# PWM_Input.net
KiCad netlist of a schematic drawn in Altium Designer
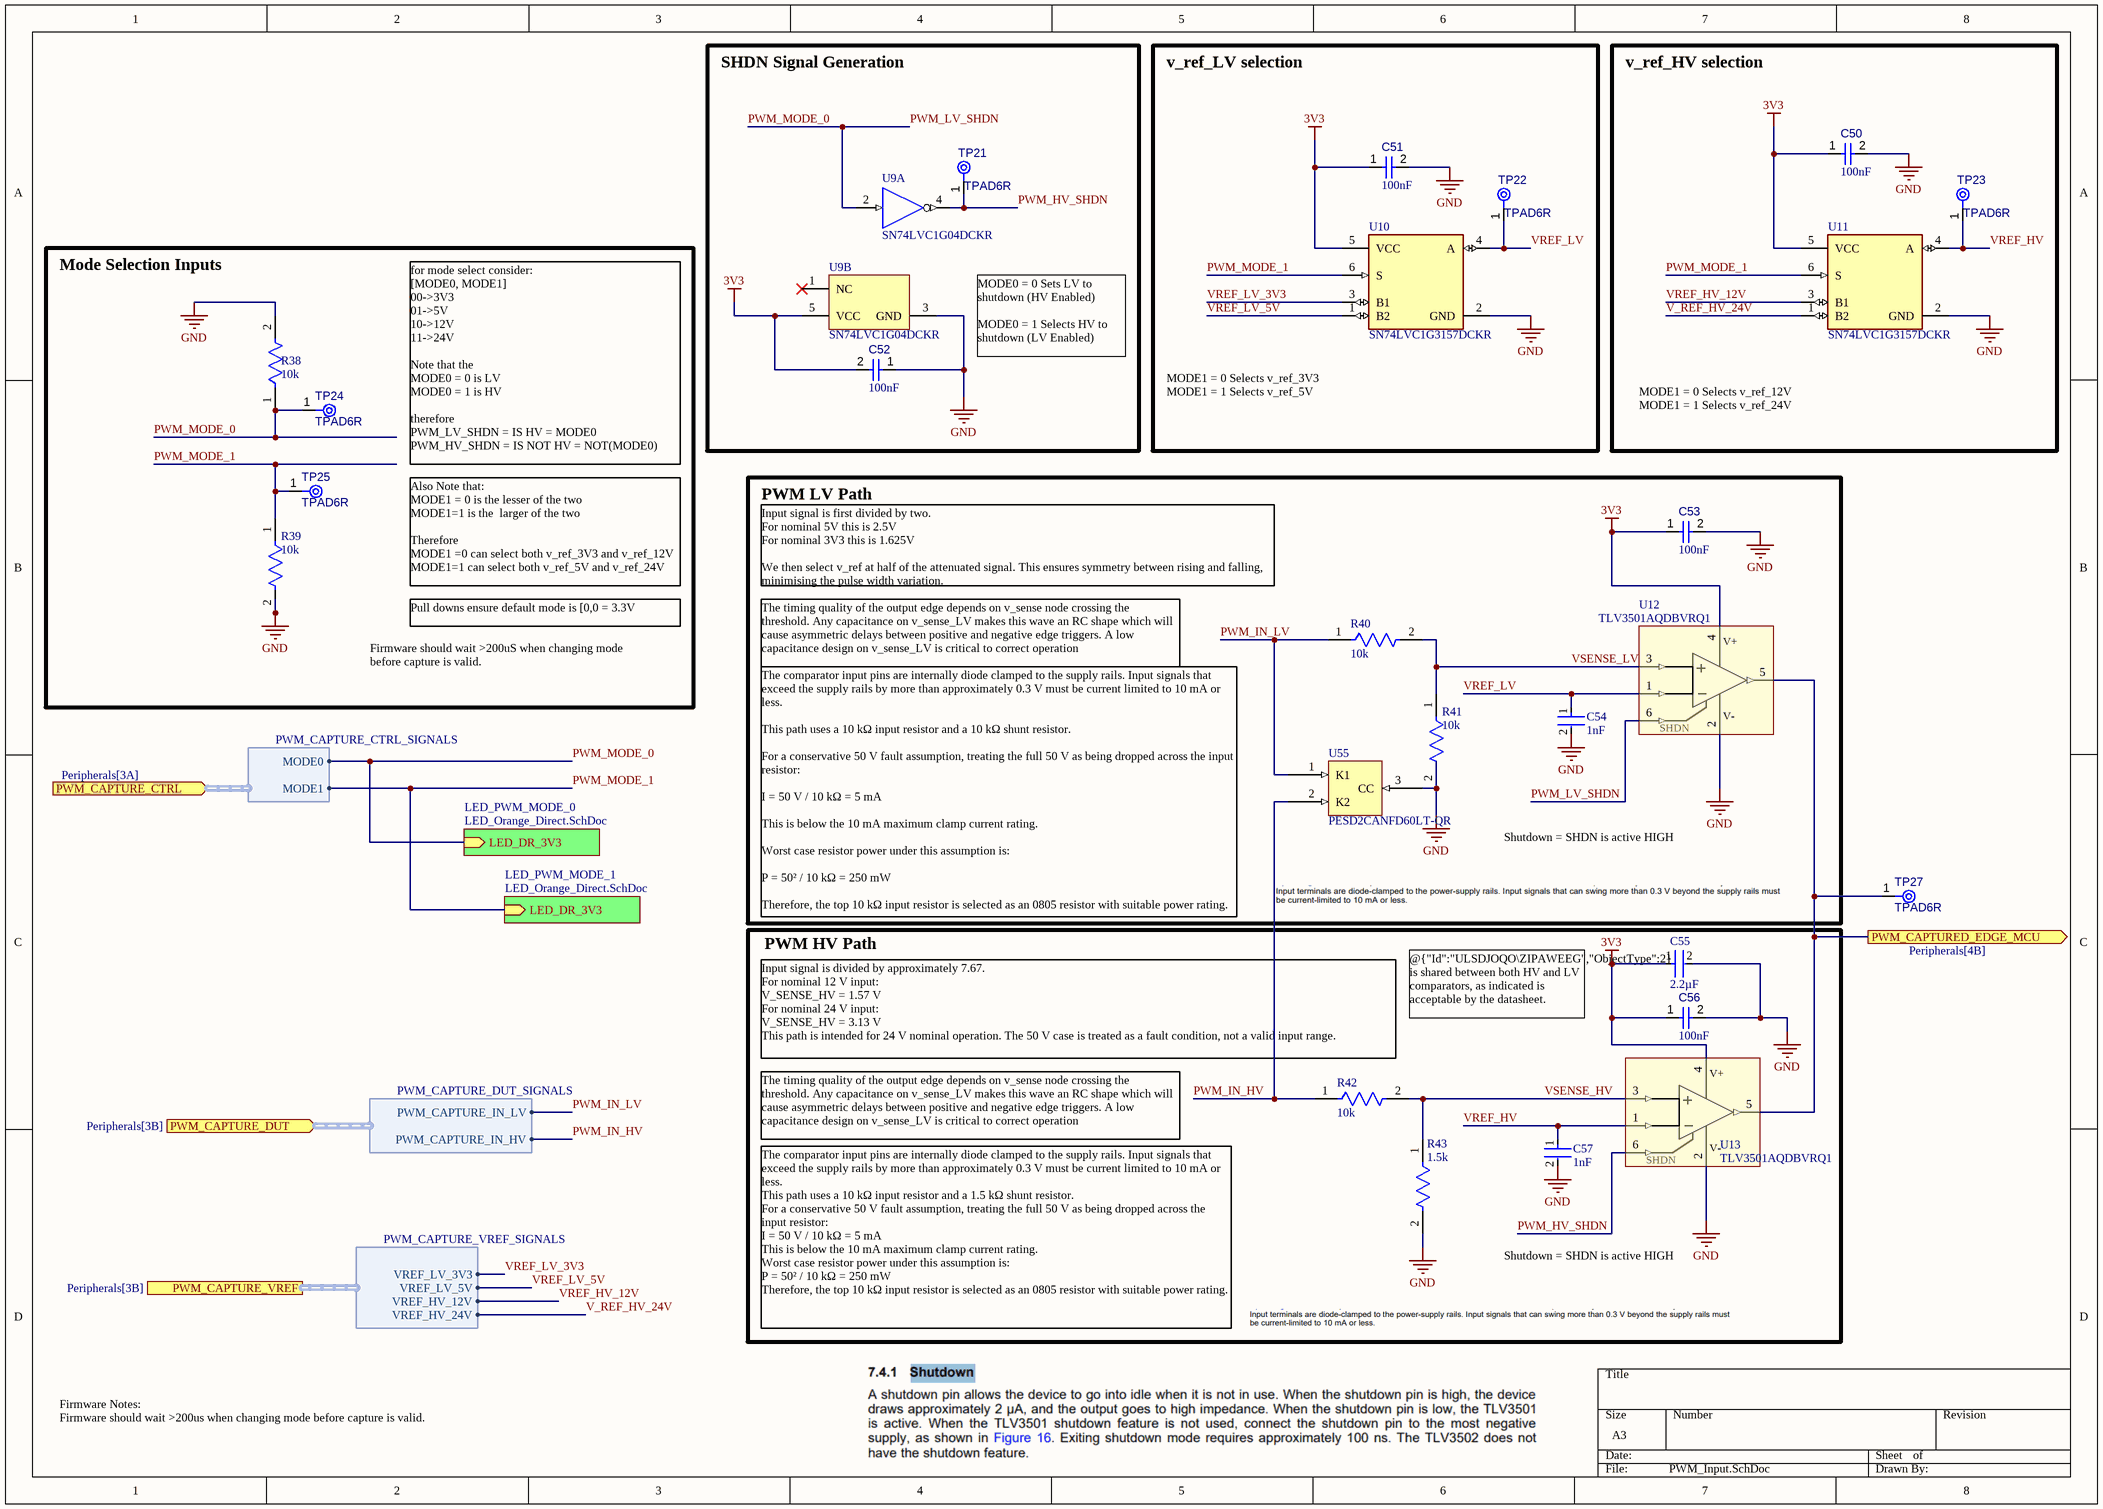
[diagram p0:  PWM_Input.SchDoc]

(export (version "E")
  (design (tool "Eeschema 10.0.6"))
  (components
    (comp (ref "C50")
      (value "100nF")
      (footprint "CAPC1608X90X40ML10T20")
      (description "Chip Capacitor, 100 nF, +/- 10%, 50 V, 0603 (1608 Metric)")
      (fields (field (name "TOLERANCE") "10%") (field (name "Comment") "Capacitor 100 nF +/-10% 50 V 0603"))
      (libsource (lib "HIL RIG FYP") (part "CAP-NP-2"))
    )
    (comp (ref "C51")
      (value "100nF")
      (footprint "CAPC1608X90X40NL10T20")
      (description "Chip Capacitor, 100 nF, +/- 10%, 50 V, 0603 (1608 Metric)")
      (fields (field (name "TOLERANCE") "10%") (field (name "Comment") "Capacitor 100 nF +/-10% 50 V 0603"))
      (libsource (lib "HIL RIG FYP") (part "CAP-NP-2"))
    )
    (comp (ref "C52")
      (value "100nF")
      (footprint "CAPC1608X90X40ML10T20")
      (description "Chip Capacitor, 100 nF, +/- 10%, 50 V, 0603 (1608 Metric)")
      (fields (field (name "TOLERANCE") "10%") (field (name "Comment") "Capacitor 100 nF +/-10% 50 V 0603"))
      (libsource (lib "HIL RIG FYP") (part "CAP-NP-2"))
    )
    (comp (ref "C53")
      (value "100nF")
      (footprint "CAPC1608X90X40ML10T20")
      (description "Chip Capacitor, 100 nF, +/- 10%, 50 V, 0603 (1608 Metric)")
      (fields (field (name "TOLERANCE") "10%") (field (name "Comment") "Capacitor 100 nF +/-10% 50 V 0603"))
      (libsource (lib "HIL RIG FYP") (part "CAP-NP-2"))
    )
    (comp (ref "C54")
      (value "1nF")
      (footprint "FP-CC0603-DA-IPC_B")
      (description "16V 1nF X7R ±10% 0603 Multilayer Ceramic Capacitors MLCC - SMD/SMT ROHS")
      (fields (field (name "TOLERANCE") "10%") (field (name "Comment") "CC0603KRX7R7BB102"))
      (libsource (lib "HIL RIG FYP") (part "11868f565c42a9108669ba33697ecf6"))
    )
    (comp (ref "C55")
      (value "2.2µF")
      (footprint "FP-GRM188-0_1-e0_2_0_5-IPC_B")
      (description "10V 2.2uF X7R ±10% 0603 Multilayer Ceramic Capacitors MLCC - SMD/SMT ROHS")
      (fields (field (name "VOLTAGE") "10V") (field (name "TOLERANCE") "10%"))
      (libsource (lib "HIL RIG FYP") (part "11868f565c42a9108669ba33697ecf6"))
    )
    (comp (ref "C56")
      (value "100nF")
      (footprint "CAPC1608X90X40ML10T20")
      (description "Chip Capacitor, 100 nF, +/- 10%, 50 V, 0603 (1608 Metric)")
      (fields (field (name "TOLERANCE") "10%") (field (name "Comment") "Capacitor 100 nF +/-10% 50 V 0603"))
      (libsource (lib "HIL RIG FYP") (part "CAP-NP-2"))
    )
    (comp (ref "C57")
      (value "1nF")
      (footprint "FP-CC0603-DA-IPC_B")
      (description "16V 1nF X7R ±10% 0603 Multilayer Ceramic Capacitors MLCC - SMD/SMT ROHS")
      (fields (field (name "TOLERANCE") "10%") (field (name "Comment") "CC0603KRX7R7BB102"))
      (libsource (lib "HIL RIG FYP") (part "11868f565c42a9108669ba33697ecf6"))
    )
    (comp (ref "R38")
      (value "10k")
      (footprint "FP-RT0603-IPC_C")
      (description "Res Thin Film 0603 10K Ohm 0.1% 1/10W ¦25ppm/¦C SMD Paper T/R")
      (fields (field (name "TOLERANCE") "0.1%") (field (name "Comment") "RT0603BRD0710KL"))
      (libsource (lib "HIL RIG FYP") (part "1029c3af85768c4190bb7ad29bc67b5"))
    )
    (comp (ref "R39")
      (value "10k")
      (footprint "FP-RT0603-IPC_A")
      (description "Res Thin Film 0603 10K Ohm 0.1% 1/10W ¦25ppm/¦C SMD Paper T/R")
      (fields (field (name "TOLERANCE") "0.1%") (field (name "Comment") "RT0603BRD0710KL"))
      (libsource (lib "HIL RIG FYP") (part "1029c3af85768c4190bb7ad29bc67b5"))
    )
    (comp (ref "R40")
      (value "10k")
      (footprint "FP-ESR18-IPC_A")
      (description "Res Thick Film 1206 10K Ohm 1% 0.5W(1/2W) ±100ppm/C Pad SMD T/R Automotive AEC-Q200")
      (fields (field (name "TOLERANCE") "1%") (field (name "Comment") "ESR18EZPF1002"))
      (libsource (lib "HIL RIG FYP") (part "1029c3af85768c4190bb7ad29bc67b5"))
    )
    (comp (ref "R41")
      (value "10k")
      (footprint "FP-RT0603-IPC_A")
      (description "Res Thin Film 0603 10K Ohm 0.1% 1/10W ¦25ppm/¦C SMD Paper T/R")
      (fields (field (name "TOLERANCE") "0.1%") (field (name "Comment") "RT0603BRD0710KL"))
      (libsource (lib "HIL RIG FYP") (part "1029c3af85768c4190bb7ad29bc67b5"))
    )
    (comp (ref "R42")
      (value "10k")
      (footprint "FP-ESR18-IPC_A")
      (description "Res Thick Film 1206 10K Ohm 1% 0.5W(1/2W) ±100ppm/C Pad SMD T/R Automotive AEC-Q200")
      (fields (field (name "TOLERANCE") "1%") (field (name "Comment") "ESR18EZPF1002"))
      (libsource (lib "HIL RIG FYP") (part "1029c3af85768c4190bb7ad29bc67b5"))
    )
    (comp (ref "R43")
      (value "1.5k")
      (footprint "FP-RT0603-IPC_C")
      (description "Res Thin Film 0603 1.5K Ohm 0.1% 1/10W ±25ppm/°C Molded SMD SMD Paper T/R")
      (fields (field (name "TOLERANCE") "0.1%") (field (name "Comment") "RT0603BRD071K5L"))
      (libsource (lib "HIL RIG FYP") (part "1029c3af85768c4190bb7ad29bc67b5"))
    )
    (comp (ref "TP21")
      (value "TPAD6R")
      (footprint "TP06R")
      (description "0.6mm round")
      (libsource (lib "HIL RIG FYP") (part "CMP-001-0001-4"))
    )
    (comp (ref "TP22")
      (value "TPAD6R")
      (footprint "TP06R")
      (description "0.6mm round")
      (libsource (lib "HIL RIG FYP") (part "CMP-001-0001-4"))
    )
    (comp (ref "TP23")
      (value "TPAD6R")
      (footprint "TP06R")
      (description "0.6mm round")
      (libsource (lib "HIL RIG FYP") (part "CMP-001-0001-4"))
    )
    (comp (ref "TP24")
      (value "TPAD6R")
      (footprint "TP06R")
      (description "0.6mm round")
      (libsource (lib "HIL RIG FYP") (part "CMP-001-0001-4"))
    )
    (comp (ref "TP25")
      (value "TPAD6R")
      (footprint "TP06R")
      (description "0.6mm round")
      (libsource (lib "HIL RIG FYP") (part "CMP-001-0001-4"))
    )
    (comp (ref "TP27")
      (value "TPAD6R")
      (footprint "TP06R")
      (description "0.6mm round")
      (libsource (lib "HIL RIG FYP") (part "CMP-001-0001-4"))
    )
    (comp (ref "U9")
      (value "SN74LVC1G04DCKR")
      (footprint "DCK0005A_N")
      (description "IC SINGLE INVERTER GATE SC70-5 / Inverter 1-Element CMOS 5-Pin SC-70 T/R")
      (libsource (lib "HIL RIG FYP") (part "TI-SN74XXX1XX4-XX-5"))
    )
    (comp (ref "U10")
      (value "SN74LVC1G3157DCKR")
      (footprint "FP-DCK0006A-MFG")
      (description "Single-pole Double-throw Analog Switch SPDT, 1 Func, 1 Channel, Cmos, PDSO6")
      (libsource (lib "HIL RIG FYP") (part "0261a57985ab8eeec66806cf7caee19"))
    )
    (comp (ref "U11")
      (value "SN74LVC1G3157DCKR")
      (footprint "FP-DCK0006A-MFG")
      (description "Single-pole Double-throw Analog Switch SPDT, 1 Func, 1 Channel, Cmos, PDSO6")
      (libsource (lib "HIL RIG FYP") (part "0261a57985ab8eeec66806cf7caee19"))
    )
    (comp (ref "U12")
      (value "TLV3501AQDBVRQ1")
      (footprint "SOT95P280X145-6M")
      (fields (field (name "COPYRIGHT") "Copyright (C) 2025 Ultra Librarian. All rights reserved."))
      (libsource (lib "HIL RIG FYP") (part "TLV3501AQDBVRQ1"))
    )
    (comp (ref "U13")
      (value "TLV3501AQDBVRQ1")
      (footprint "SOT95P280X145-6M")
      (fields (field (name "COPYRIGHT") "Copyright (C) 2025 Ultra Librarian. All rights reserved."))
      (libsource (lib "HIL RIG FYP") (part "TLV3501AQDBVRQ1"))
    )
    (comp (ref "U55")
      (value "PESD2CANFD60LT-QR")
      (footprint "SOT95P230X110-3M")
      (description "Esd Protection Device, 79V, SOT-23-3 Rohs Compliant: Yes")
      (libsource (lib "HIL RIG FYP") (part "PESD2CANFD60LT-QR-Symbol-1"))
    )
  )
  (nets
    (net (code "4") (name "/PWM_CAPTURED_EDGE_MCU") (class "Default")
      (node (ref "TP27") (pin "1") (pinfunction "TP_1") (pintype "passive"))
      (node (ref "U12") (pin "5") (pinfunction "OUT_5") (pintype "output"))
      (node (ref "U13") (pin "5") (pinfunction "OUT_5") (pintype "output"))
    )
    (net (code "5") (name "/PWM_HV_SHDN") (class "Default")
      (node (ref "TP21") (pin "1") (pinfunction "TP_1") (pintype "passive"))
      (node (ref "U13") (pin "6") (pinfunction "SD_6") (pintype "input"))
      (node (ref "U9") (pin "4") (pinfunction "Y_4") (pintype "output"))
    )
    (net (code "6") (name "/PWM_IN_HV") (class "Default")
      (node (ref "R42") (pin "1") (pinfunction "1_1") (pintype "passive"))
      (node (ref "U55") (pin "2") (pinfunction "K2_2") (pintype "input"))
    )
    (net (code "7") (name "/PWM_IN_LV") (class "Default")
      (node (ref "R40") (pin "1") (pinfunction "1_1") (pintype "passive"))
      (node (ref "U55") (pin "1") (pinfunction "K1_1") (pintype "input"))
    )
    (net (code "8") (name "/PWM_LV_SHDN") (class "Default")
      (node (ref "R38") (pin "1") (pinfunction "1_1") (pintype "passive"))
      (node (ref "TP24") (pin "1") (pinfunction "TP_1") (pintype "passive"))
      (node (ref "U12") (pin "6") (pinfunction "SD_6") (pintype "input"))
      (node (ref "U9") (pin "2") (pinfunction "A_2") (pintype "input"))
    )
    (net (code "9") (name "/PWM_MODE_1") (class "Default")
      (node (ref "R39") (pin "1") (pinfunction "1_1") (pintype "passive"))
      (node (ref "TP25") (pin "1") (pinfunction "TP_1") (pintype "passive"))
      (node (ref "U10") (pin "6") (pinfunction "S_6") (pintype "input"))
      (node (ref "U11") (pin "6") (pinfunction "S_6") (pintype "input"))
    )
    (net (code "10") (name "/VREF_HV") (class "Default")
      (node (ref "C57") (pin "1") (pinfunction "1_1") (pintype "passive"))
      (node (ref "TP23") (pin "1") (pinfunction "TP_1") (pintype "passive"))
      (node (ref "U11") (pin "4") (pinfunction "A_4") (pintype "bidirectional"))
      (node (ref "U13") (pin "1") (pinfunction "IN-_1") (pintype "input"))
    )
    (net (code "11") (name "/VREF_HV_12V") (class "Default")
      (node (ref "U11") (pin "3") (pinfunction "B1_3") (pintype "bidirectional"))
    )
    (net (code "12") (name "/VREF_LV") (class "Default")
      (node (ref "C54") (pin "1") (pinfunction "1_1") (pintype "passive"))
      (node (ref "TP22") (pin "1") (pinfunction "TP_1") (pintype "passive"))
      (node (ref "U10") (pin "4") (pinfunction "A_4") (pintype "bidirectional"))
      (node (ref "U12") (pin "1") (pinfunction "IN-_1") (pintype "input"))
    )
    (net (code "13") (name "/VREF_LV_3V3") (class "Default")
      (node (ref "U10") (pin "3") (pinfunction "B1_3") (pintype "bidirectional"))
    )
    (net (code "14") (name "/VREF_LV_5V") (class "Default")
      (node (ref "U10") (pin "1") (pinfunction "B2_1") (pintype "bidirectional"))
    )
    (net (code "15") (name "/VSENSE_HV") (class "Default")
      (node (ref "R42") (pin "2") (pinfunction "2_2") (pintype "passive"))
      (node (ref "R43") (pin "1") (pinfunction "1_1") (pintype "passive"))
      (node (ref "U13") (pin "3") (pinfunction "IN+_3") (pintype "input"))
    )
    (net (code "16") (name "/VSENSE_LV") (class "Default")
      (node (ref "R40") (pin "2") (pinfunction "2_2") (pintype "passive"))
      (node (ref "R41") (pin "1") (pinfunction "1_1") (pintype "passive"))
      (node (ref "U12") (pin "3") (pinfunction "IN+_3") (pintype "input"))
    )
    (net (code "17") (name "/V_REF_HV_24V") (class "Default")
      (node (ref "U11") (pin "1") (pinfunction "B2_1") (pintype "bidirectional"))
    )
    (net (code "21") (name "3V3") (class "Default")
      (node (ref "C50") (pin "1") (pinfunction "1_1") (pintype "passive"))
      (node (ref "C51") (pin "1") (pinfunction "1_1") (pintype "passive"))
      (node (ref "C52") (pin "2") (pinfunction "2_2") (pintype "passive"))
      (node (ref "C53") (pin "1") (pinfunction "1_1") (pintype "passive"))
      (node (ref "C55") (pin "1") (pinfunction "1_1") (pintype "passive"))
      (node (ref "C56") (pin "1") (pinfunction "1_1") (pintype "passive"))
      (node (ref "U10") (pin "5") (pinfunction "VCC_5") (pintype "power_in"))
      (node (ref "U11") (pin "5") (pinfunction "VCC_5") (pintype "power_in"))
      (node (ref "U12") (pin "4") (pinfunction "V+_4") (pintype "power_in"))
      (node (ref "U13") (pin "4") (pinfunction "V+_4") (pintype "power_in"))
      (node (ref "U9") (pin "5") (pinfunction "VCC_5") (pintype "power_in"))
    )
    (net (code "22") (name "GND") (class "Default")
      (node (ref "C50") (pin "2") (pinfunction "2_2") (pintype "passive"))
      (node (ref "C51") (pin "2") (pinfunction "2_2") (pintype "passive"))
      (node (ref "C52") (pin "1") (pinfunction "1_1") (pintype "passive"))
      (node (ref "C53") (pin "2") (pinfunction "2_2") (pintype "passive"))
      (node (ref "C54") (pin "2") (pinfunction "2_2") (pintype "passive"))
      (node (ref "C55") (pin "2") (pinfunction "2_2") (pintype "passive"))
      (node (ref "C56") (pin "2") (pinfunction "2_2") (pintype "passive"))
      (node (ref "C57") (pin "2") (pinfunction "2_2") (pintype "passive"))
      (node (ref "R38") (pin "2") (pinfunction "2_2") (pintype "passive"))
      (node (ref "R39") (pin "2") (pinfunction "2_2") (pintype "passive"))
      (node (ref "R41") (pin "2") (pinfunction "2_2") (pintype "passive"))
      (node (ref "R43") (pin "2") (pinfunction "2_2") (pintype "passive"))
      (node (ref "U10") (pin "2") (pinfunction "GND_2") (pintype "power_in"))
      (node (ref "U11") (pin "2") (pinfunction "GND_2") (pintype "power_in"))
      (node (ref "U12") (pin "2") (pinfunction "V-_2") (pintype "power_in"))
      (node (ref "U13") (pin "2") (pinfunction "V-_2") (pintype "power_in"))
      (node (ref "U55") (pin "3") (pinfunction "CC_3") (pintype "input"))
      (node (ref "U9") (pin "3") (pinfunction "GND_3") (pintype "power_in"))
    )
    (net (code "23") (name "unconnected-(U9B-NC-Pad1)") (class "Default")
      (node (ref "U9") (pin "1") (pinfunction "NC_1") (pintype "passive+no_connect"))
    )
  )
)
